# MezcladorBF998.net
KiCad netlist of a schematic drawn in Altium Designer
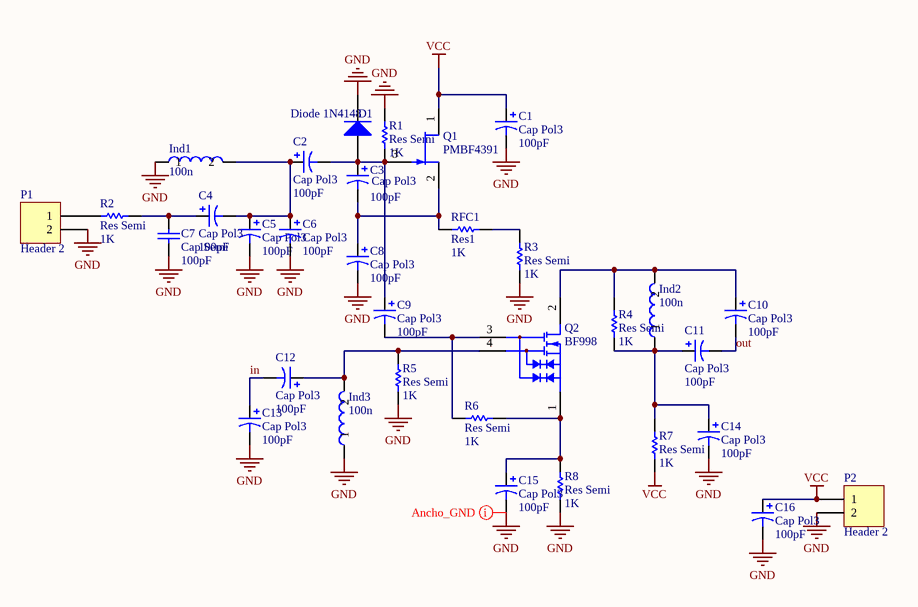
[diagram p0: MezcladorBF998.SchDoc]

(export (version "E")
  (design (tool "Eeschema 10.0.6"))
  (components
    (comp (ref "C1")
      (value "Cap Pol3")
      (footprint "C0805")
      (description "Polarized Capacitor (Surface Mount)")
      (fields (field (name "ALTIUM_VALUE") "100pF") (field (name "PUBLISHER") "Altium Limited"))
      (libsource (lib "Miscellaneous Devices") (part "Cap Pol3"))
    )
    (comp (ref "C2")
      (value "Cap Pol3")
      (footprint "C0805")
      (description "Polarized Capacitor (Surface Mount)")
      (fields (field (name "ALTIUM_VALUE") "100pF") (field (name "PUBLISHER") "Altium Limited"))
      (libsource (lib "Miscellaneous Devices") (part "Cap Pol3"))
    )
    (comp (ref "C3")
      (value "Cap Pol3")
      (footprint "C0805")
      (description "Polarized Capacitor (Surface Mount)")
      (fields (field (name "ALTIUM_VALUE") "100pF") (field (name "PUBLISHER") "Altium Limited"))
      (libsource (lib "Miscellaneous Devices") (part "Cap Pol3"))
    )
    (comp (ref "C4")
      (value "Cap Pol3")
      (footprint "C0805")
      (description "Polarized Capacitor (Surface Mount)")
      (fields (field (name "ALTIUM_VALUE") "100pF") (field (name "PUBLISHER") "Altium Limited"))
      (libsource (lib "Miscellaneous Devices") (part "Cap Pol3"))
    )
    (comp (ref "C5")
      (value "Cap Pol3")
      (footprint "C0805")
      (description "Polarized Capacitor (Surface Mount)")
      (fields (field (name "ALTIUM_VALUE") "100pF") (field (name "PUBLISHER") "Altium Limited"))
      (libsource (lib "Miscellaneous Devices") (part "Cap Pol3"))
    )
    (comp (ref "C6")
      (value "Cap Pol3")
      (footprint "C0805")
      (description "Polarized Capacitor (Surface Mount)")
      (fields (field (name "ALTIUM_VALUE") "100pF") (field (name "PUBLISHER") "Altium Limited"))
      (libsource (lib "Miscellaneous Devices") (part "Cap Pol3"))
    )
    (comp (ref "C7")
      (value "Cap Semi")
      (footprint "C1206")
      (description "Capacitor (Semiconductor SIM Model)")
      (fields (field (name "ALTIUM_VALUE") "100pF") (field (name "PUBLISHER") "Altium Limited"))
      (libsource (lib "Miscellaneous Devices") (part "Cap Semi"))
    )
    (comp (ref "C8")
      (value "Cap Pol3")
      (footprint "C0805")
      (description "Polarized Capacitor (Surface Mount)")
      (fields (field (name "ALTIUM_VALUE") "100pF") (field (name "PUBLISHER") "Altium Limited"))
      (libsource (lib "Miscellaneous Devices") (part "Cap Pol3"))
    )
    (comp (ref "C9")
      (value "Cap Pol3")
      (footprint "C0805")
      (description "Polarized Capacitor (Surface Mount)")
      (fields (field (name "ALTIUM_VALUE") "100pF") (field (name "PUBLISHER") "Altium Limited"))
      (libsource (lib "Miscellaneous Devices") (part "Cap Pol3"))
    )
    (comp (ref "C10")
      (value "Cap Pol3")
      (footprint "C0805")
      (description "Polarized Capacitor (Surface Mount)")
      (fields (field (name "ALTIUM_VALUE") "100pF") (field (name "PUBLISHER") "Altium Limited"))
      (libsource (lib "Miscellaneous Devices") (part "Cap Pol3"))
    )
    (comp (ref "C11")
      (value "Cap Pol3")
      (footprint "C0805")
      (description "Polarized Capacitor (Surface Mount)")
      (fields (field (name "ALTIUM_VALUE") "100pF") (field (name "PUBLISHER") "Altium Limited"))
      (libsource (lib "Miscellaneous Devices") (part "Cap Pol3"))
    )
    (comp (ref "C12")
      (value "Cap Pol3")
      (footprint "C0805")
      (description "Polarized Capacitor (Surface Mount)")
      (fields (field (name "ALTIUM_VALUE") "100pF") (field (name "PUBLISHER") "Altium Limited"))
      (libsource (lib "Miscellaneous Devices") (part "Cap Pol3"))
    )
    (comp (ref "C13")
      (value "Cap Pol3")
      (footprint "C0805")
      (description "Polarized Capacitor (Surface Mount)")
      (fields (field (name "ALTIUM_VALUE") "100pF") (field (name "PUBLISHER") "Altium Limited"))
      (libsource (lib "Miscellaneous Devices") (part "Cap Pol3"))
    )
    (comp (ref "C14")
      (value "Cap Pol3")
      (footprint "C0805")
      (description "Polarized Capacitor (Surface Mount)")
      (fields (field (name "ALTIUM_VALUE") "100pF") (field (name "PUBLISHER") "Altium Limited"))
      (libsource (lib "Miscellaneous Devices") (part "Cap Pol3"))
    )
    (comp (ref "C15")
      (value "Cap Pol3")
      (footprint "C0805")
      (description "Polarized Capacitor (Surface Mount)")
      (fields (field (name "ALTIUM_VALUE") "100pF") (field (name "PUBLISHER") "Altium Limited"))
      (libsource (lib "Miscellaneous Devices") (part "Cap Pol3"))
    )
    (comp (ref "C16")
      (value "Cap Pol3")
      (footprint "C0805")
      (description "Polarized Capacitor (Surface Mount)")
      (fields (field (name "ALTIUM_VALUE") "100pF") (field (name "PUBLISHER") "Altium Limited"))
      (libsource (lib "Miscellaneous Devices") (part "Cap Pol3"))
    )
    (comp (ref "D1")
      (value "Diode 1N4148")
      (footprint "DO-35")
      (description "High Conductance Fast Diode")
      (fields (field (name "PUBLISHER") "Altium Limited"))
      (libsource (lib "Miscellaneous Devices") (part "Diode 1N4148"))
    )
    (comp (ref "Ind1")
      (value "Ind2")
      (footprint "Ind_3mm")
      (fields (field (name "VALOR") "100n"))
      (libsource (lib "epf") (part "Ind2"))
    )
    (comp (ref "Ind2")
      (value "Ind2")
      (footprint "IND_7MM")
      (fields (field (name "VALOR") "100n"))
      (libsource (lib "epf") (part "Ind2"))
    )
    (comp (ref "Ind3")
      (value "Ind2")
      (footprint "Ind_4mm")
      (fields (field (name "VALOR") "100n"))
      (libsource (lib "epf") (part "Ind2"))
    )
    (comp (ref "P1")
      (value "Header 2")
      (footprint "HDR1X2")
      (description "Header, 2-Pin")
      (fields (field (name "PUBLISHER") "Altium Limited"))
      (libsource (lib "Miscellaneous Connectors") (part "Header 2"))
    )
    (comp (ref "P2")
      (value "Header 2")
      (footprint "HDR1X2")
      (description "Header, 2-Pin")
      (fields (field (name "PUBLISHER") "Altium Limited"))
      (libsource (lib "") (part "Header 2_1"))
    )
    (comp (ref "Q1")
      (value "PMBF4391")
      (footprint "SOT23")
      (description "N-channel Silicon Junction Field-effect Transistor")
      (fields (field (name "PUBLISHER") "Altium Limited"))
      (libsource (lib "Philips Discrete JFET") (part "PMBF4391"))
    )
    (comp (ref "Q2")
      (value "BF998")
      (footprint "SOT143")
      (description "Silicon N-channel Dual-gate MOSFET")
      (fields (field (name "PUBLISHER") "Altium Limited"))
      (libsource (lib "Philips Discrete MOSFET - Low Power") (part "BF998"))
    )
    (comp (ref "R1")
      (value "Res Semi")
      (footprint "2012[0805]")
      (description "Semiconductor Resistor")
      (fields (field (name "ALTIUM_VALUE") "1K") (field (name "PUBLISHER") "Altium Limited"))
      (libsource (lib "Miscellaneous Devices") (part "Res Semi"))
    )
    (comp (ref "R2")
      (value "Res Semi")
      (footprint "2012[0805]")
      (description "Semiconductor Resistor")
      (fields (field (name "ALTIUM_VALUE") "1K") (field (name "PUBLISHER") "Altium Limited"))
      (libsource (lib "Miscellaneous Devices") (part "Res Semi"))
    )
    (comp (ref "R3")
      (value "Res Semi")
      (footprint "2012[0805]")
      (description "Semiconductor Resistor")
      (fields (field (name "ALTIUM_VALUE") "1K") (field (name "PUBLISHER") "Altium Limited"))
      (libsource (lib "Miscellaneous Devices") (part "Res Semi"))
    )
    (comp (ref "R4")
      (value "Res Semi")
      (footprint "2012[0805]")
      (description "Semiconductor Resistor")
      (fields (field (name "ALTIUM_VALUE") "1K") (field (name "PUBLISHER") "Altium Limited"))
      (libsource (lib "Miscellaneous Devices") (part "Res Semi"))
    )
    (comp (ref "R5")
      (value "Res Semi")
      (footprint "2012[0805]")
      (description "Semiconductor Resistor")
      (fields (field (name "ALTIUM_VALUE") "1K") (field (name "PUBLISHER") "Altium Limited"))
      (libsource (lib "Miscellaneous Devices") (part "Res Semi"))
    )
    (comp (ref "R6")
      (value "Res Semi")
      (footprint "2012[0805]")
      (description "Semiconductor Resistor")
      (fields (field (name "ALTIUM_VALUE") "1K") (field (name "PUBLISHER") "Altium Limited"))
      (libsource (lib "Miscellaneous Devices") (part "Res Semi"))
    )
    (comp (ref "R7")
      (value "Res Semi")
      (footprint "2012[0805]")
      (description "Semiconductor Resistor")
      (fields (field (name "ALTIUM_VALUE") "1K") (field (name "PUBLISHER") "Altium Limited"))
      (libsource (lib "Miscellaneous Devices") (part "Res Semi"))
    )
    (comp (ref "R8")
      (value "Res Semi")
      (footprint "2012[0805]")
      (description "Semiconductor Resistor")
      (fields (field (name "ALTIUM_VALUE") "1K") (field (name "PUBLISHER") "Altium Limited"))
      (libsource (lib "Miscellaneous Devices") (part "Res Semi"))
    )
    (comp (ref "RFC1")
      (value "Res1")
      (footprint "AXIAL-0.3")
      (description "Resistor")
      (fields (field (name "ALTIUM_VALUE") "1K") (field (name "PUBLISHER") "Altium Limited"))
      (libsource (lib "Miscellaneous Devices") (part "Res1"))
    )
  )
  (nets
    (net (code "1") (name "/in") (class "Default")
      (node (ref "C12") (pin "2") (pinfunction "2_2") (pintype "passive"))
      (node (ref "C13") (pin "1") (pinfunction "1_1") (pintype "passive"))
    )
    (net (code "2") (name "/out") (class "Default")
      (node (ref "C10") (pin "2") (pinfunction "2_2") (pintype "passive"))
      (node (ref "C11") (pin "2") (pinfunction "2_2") (pintype "passive"))
    )
    (net (code "3") (name "GND") (class "Default")
      (node (ref "C1") (pin "2") (pinfunction "2_2") (pintype "passive"))
      (node (ref "C13") (pin "2") (pinfunction "2_2") (pintype "passive"))
      (node (ref "C14") (pin "2") (pinfunction "2_2") (pintype "passive"))
      (node (ref "C15") (pin "2") (pinfunction "2_2") (pintype "passive"))
      (node (ref "C16") (pin "2") (pinfunction "2_2") (pintype "passive"))
      (node (ref "C5") (pin "2") (pinfunction "2_2") (pintype "passive"))
      (node (ref "C6") (pin "2") (pinfunction "2_2") (pintype "passive"))
      (node (ref "C7") (pin "2") (pinfunction "2_2") (pintype "passive"))
      (node (ref "C8") (pin "2") (pinfunction "2_2") (pintype "passive"))
      (node (ref "D1") (pin "2") (pinfunction "K_2") (pintype "passive"))
      (node (ref "Ind1") (pin "1") (pinfunction "1_1") (pintype "passive"))
      (node (ref "Ind3") (pin "1") (pinfunction "1_1") (pintype "passive"))
      (node (ref "P1") (pin "2") (pinfunction "2_2") (pintype "passive"))
      (node (ref "P2") (pin "2") (pinfunction "2_2") (pintype "passive"))
      (node (ref "R1") (pin "2") (pinfunction "2_2") (pintype "passive"))
      (node (ref "R3") (pin "1") (pinfunction "1_1") (pintype "passive"))
      (node (ref "R5") (pin "2") (pinfunction "2_2") (pintype "passive"))
      (node (ref "R8") (pin "1") (pinfunction "1_1") (pintype "passive"))
    )
    (net (code "4") (name "Net-(C2-Pad1)") (class "Default")
      (node (ref "C2") (pin "1") (pinfunction "1_1") (pintype "passive"))
      (node (ref "C4") (pin "2") (pinfunction "2_2") (pintype "passive"))
      (node (ref "C5") (pin "1") (pinfunction "1_1") (pintype "passive"))
      (node (ref "C6") (pin "1") (pinfunction "1_1") (pintype "passive"))
      (node (ref "Ind1") (pin "2") (pinfunction "2_2") (pintype "passive"))
    )
    (net (code "5") (name "Net-(C4-Pad1)") (class "Default")
      (node (ref "C4") (pin "1") (pinfunction "1_1") (pintype "passive"))
      (node (ref "C7") (pin "1") (pinfunction "1_1") (pintype "passive"))
      (node (ref "R2") (pin "2") (pinfunction "2_2") (pintype "passive"))
    )
    (net (code "6") (name "Net-(C11-Pad1)") (class "Default")
      (node (ref "C11") (pin "1") (pinfunction "1_1") (pintype "passive"))
      (node (ref "C14") (pin "1") (pinfunction "1_1") (pintype "passive"))
      (node (ref "Ind2") (pin "1") (pinfunction "1_1") (pintype "passive"))
      (node (ref "R4") (pin "2") (pinfunction "2_2") (pintype "passive"))
      (node (ref "R7") (pin "1") (pinfunction "1_1") (pintype "passive"))
    )
    (net (code "7") (name "Net-(D1-A)") (class "Default")
      (node (ref "C2") (pin "2") (pinfunction "2_2") (pintype "passive"))
      (node (ref "C3") (pin "1") (pinfunction "1_1") (pintype "passive"))
      (node (ref "C9") (pin "1") (pinfunction "1_1") (pintype "passive"))
      (node (ref "D1") (pin "1") (pinfunction "A_1") (pintype "passive"))
      (node (ref "Q1") (pin "3") (pinfunction "G_3") (pintype "passive"))
      (node (ref "R1") (pin "1") (pinfunction "1_1") (pintype "passive"))
    )
    (net (code "8") (name "Net-(P1-Pad1)") (class "Default")
      (node (ref "P1") (pin "1") (pinfunction "1_1") (pintype "passive"))
      (node (ref "R2") (pin "1") (pinfunction "1_1") (pintype "passive"))
    )
    (net (code "9") (name "Net-(Q1-S)") (class "Default")
      (node (ref "C3") (pin "2") (pinfunction "2_2") (pintype "passive"))
      (node (ref "C8") (pin "1") (pinfunction "1_1") (pintype "passive"))
      (node (ref "Q1") (pin "2") (pinfunction "S_2") (pintype "passive"))
      (node (ref "RFC1") (pin "1") (pinfunction "1_1") (pintype "passive"))
    )
    (net (code "10") (name "Net-(Q2-D)") (class "Default")
      (node (ref "C10") (pin "1") (pinfunction "1_1") (pintype "passive"))
      (node (ref "Ind2") (pin "2") (pinfunction "2_2") (pintype "passive"))
      (node (ref "Q2") (pin "2") (pinfunction "D_2") (pintype "passive"))
      (node (ref "R4") (pin "1") (pinfunction "1_1") (pintype "passive"))
    )
    (net (code "11") (name "Net-(Q2-G1)") (class "Default")
      (node (ref "C12") (pin "1") (pinfunction "1_1") (pintype "passive"))
      (node (ref "Ind3") (pin "2") (pinfunction "2_2") (pintype "passive"))
      (node (ref "Q2") (pin "4") (pinfunction "G1_4") (pintype "passive"))
      (node (ref "R5") (pin "1") (pinfunction "1_1") (pintype "passive"))
    )
    (net (code "12") (name "Net-(Q2-G2)") (class "Default")
      (node (ref "C9") (pin "2") (pinfunction "2_2") (pintype "passive"))
      (node (ref "Q2") (pin "3") (pinfunction "G2_3") (pintype "passive"))
      (node (ref "R6") (pin "2") (pinfunction "2_2") (pintype "passive"))
    )
    (net (code "13") (name "Net-(Q2-S)") (class "Default")
      (node (ref "C15") (pin "1") (pinfunction "1_1") (pintype "passive"))
      (node (ref "Q2") (pin "1") (pinfunction "S_1") (pintype "passive"))
      (node (ref "R6") (pin "1") (pinfunction "1_1") (pintype "passive"))
      (node (ref "R8") (pin "2") (pinfunction "2_2") (pintype "passive"))
    )
    (net (code "14") (name "Net-(R3-Pad2)") (class "Default")
      (node (ref "R3") (pin "2") (pinfunction "2_2") (pintype "passive"))
      (node (ref "RFC1") (pin "2") (pinfunction "2_2") (pintype "passive"))
    )
    (net (code "15") (name "VCC") (class "Default")
      (node (ref "C1") (pin "1") (pinfunction "1_1") (pintype "passive"))
      (node (ref "C16") (pin "1") (pinfunction "1_1") (pintype "passive"))
      (node (ref "P2") (pin "1") (pinfunction "1_1") (pintype "passive"))
      (node (ref "Q1") (pin "1") (pinfunction "D_1") (pintype "passive"))
      (node (ref "R7") (pin "2") (pinfunction "2_2") (pintype "passive"))
    )
  )
)
